# SCH_oscilliscope_copy_2021-09-11.net
KiCad netlist of a schematic drawn in EasyEDA
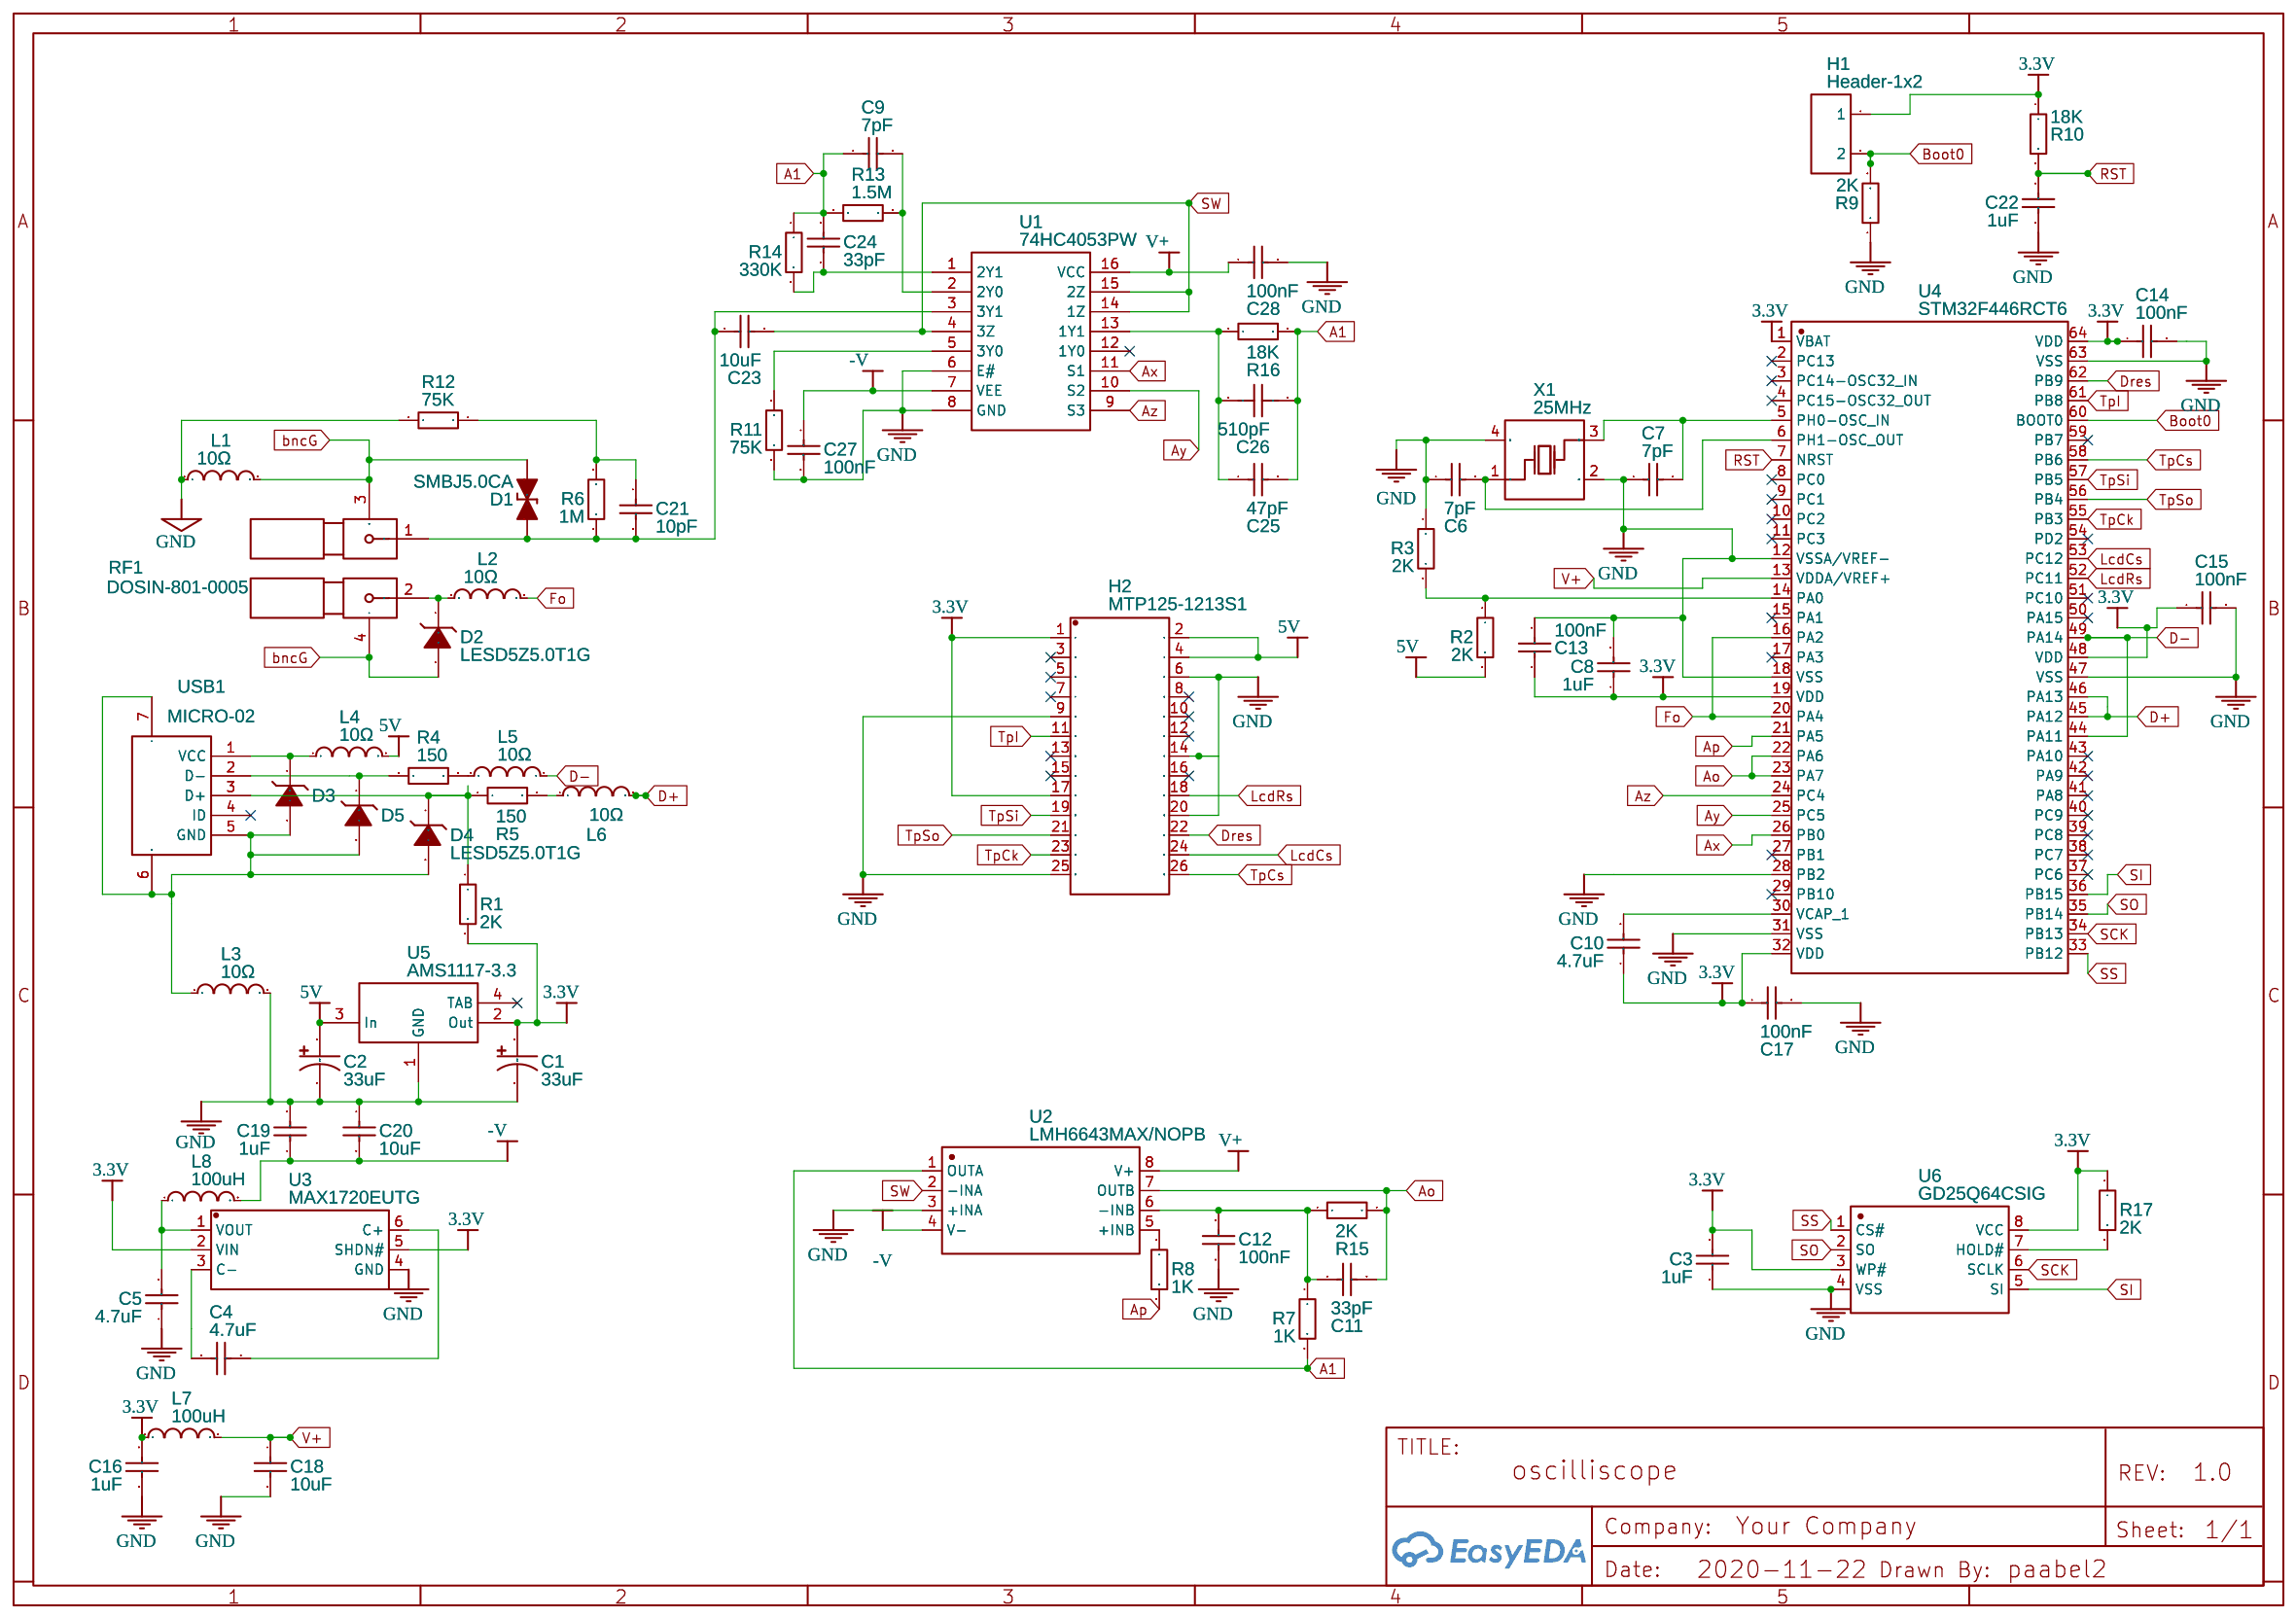
[diagram p0: schematic sheet]

(export (version "E")
  (design (tool "Eeschema 10.0.6"))
  (components
    (comp (ref "C1")
      (value "33uF")
      (fields
        (field (name "BOM_Manufacturer Part") "TC211A336M006Y")
        (field (name "BOM_Supplier Part") "C128344")
      )
      (libsource (lib "") (part "TC211A336M006Y"))
    )
    (comp (ref "C2")
      (value "33uF")
      (fields
        (field (name "BOM_Manufacturer Part") "TC211A336M006Y")
        (field (name "BOM_Supplier Part") "C128344")
      )
      (libsource (lib "") (part "TC211A336M006Y"))
    )
    (comp (ref "C3")
      (value "1uF")
      (fields
        (field (name "BOM_Manufacturer Part") "CL05A105KP5NNNC")
        (field (name "BOM_Supplier Part") "C14445")
      )
      (libsource (lib "") (part "CL05A105KP5NNNC"))
    )
    (comp (ref "C4")
      (value "4.7uF")
      (fields
        (field (name "BOM_Manufacturer Part") "CL21A475KAQNNNE")
        (field (name "BOM_Supplier Part") "C1779")
      )
      (libsource (lib "") (part "CL21A475KAQNNNE_1"))
    )
    (comp (ref "C5")
      (value "4.7uF")
      (fields
        (field (name "BOM_Manufacturer Part") "CL21A475KAQNNNE")
        (field (name "BOM_Supplier Part") "C1779")
      )
      (libsource (lib "") (part "CL21A475KAQNNNE"))
    )
    (comp (ref "C6")
      (value "7pF")
      (fields
        (field (name "BOM_Manufacturer Part") "0402CG7R0C500NT")
        (field (name "BOM_Supplier Part") "C1577")
      )
      (libsource (lib "") (part "0402CG7R0C500NT"))
    )
    (comp (ref "C7")
      (value "7pF")
      (fields
        (field (name "BOM_Manufacturer Part") "0402CG7R0C500NT")
        (field (name "BOM_Supplier Part") "C1577")
      )
      (libsource (lib "") (part "0402CG7R0C500NT"))
    )
    (comp (ref "C8")
      (value "1uF")
      (fields
        (field (name "BOM_Manufacturer Part") "CL05A105KP5NNNC")
        (field (name "BOM_Supplier Part") "C14445")
      )
      (libsource (lib "") (part "CL05A105KP5NNNC"))
    )
    (comp (ref "C9")
      (value "7pF")
      (fields
        (field (name "BOM_Manufacturer Part") "0402CG7R0C500NT")
        (field (name "BOM_Supplier Part") "C1577")
      )
      (libsource (lib "") (part "0402CG7R0C500NT"))
    )
    (comp (ref "C10")
      (value "4.7uF")
      (fields
        (field (name "BOM_Manufacturer Part") "CL21A475KAQNNNE")
        (field (name "BOM_Supplier Part") "C1779")
      )
      (libsource (lib "") (part "CL21A475KAQNNNE"))
    )
    (comp (ref "C11")
      (value "33pF")
      (fields
        (field (name "BOM_Manufacturer Part") "0402CG330J500NT")
        (field (name "BOM_Supplier Part") "C1562")
      )
      (libsource (lib "") (part "0402CG330J500NT"))
    )
    (comp (ref "C12")
      (value "100nF")
      (fields
        (field (name "BOM_Manufacturer Part") "CL05B104KO5NNNC")
        (field (name "BOM_Supplier Part") "C1525")
      )
      (libsource (lib "") (part "CL05B104KO5NNNC"))
    )
    (comp (ref "C13")
      (value "100nF")
      (fields
        (field (name "BOM_Manufacturer Part") "CL05B104KO5NNNC")
        (field (name "BOM_Supplier Part") "C1525")
      )
      (libsource (lib "") (part "CL05B104KO5NNNC_2"))
    )
    (comp (ref "C14")
      (value "100nF")
      (fields
        (field (name "BOM_Manufacturer Part") "CL05B104KO5NNNC")
        (field (name "BOM_Supplier Part") "C1525")
      )
      (libsource (lib "") (part "CL05B104KO5NNNC_1"))
    )
    (comp (ref "C15")
      (value "100nF")
      (fields
        (field (name "BOM_Manufacturer Part") "CL05B104KO5NNNC")
        (field (name "BOM_Supplier Part") "C1525")
      )
      (libsource (lib "") (part "CL05B104KO5NNNC_1"))
    )
    (comp (ref "C16")
      (value "1uF")
      (fields
        (field (name "BOM_Manufacturer Part") "CL05A105KP5NNNC")
        (field (name "BOM_Supplier Part") "C14445")
      )
      (libsource (lib "") (part "CL05A105KP5NNNC"))
    )
    (comp (ref "C17")
      (value "100nF")
      (fields
        (field (name "BOM_Manufacturer Part") "CL05B104KO5NNNC")
        (field (name "BOM_Supplier Part") "C1525")
      )
      (libsource (lib "") (part "CL05B104KO5NNNC_1"))
    )
    (comp (ref "C18")
      (value "10uF")
      (fields
        (field (name "BOM_Manufacturer Part") "CL21A106KAYNNNE")
        (field (name "BOM_Supplier Part") "C15850")
      )
      (libsource (lib "") (part "CL21A106KAYNNNE"))
    )
    (comp (ref "C19")
      (value "1uF")
      (fields
        (field (name "BOM_Manufacturer Part") "CL05A105KP5NNNC")
        (field (name "BOM_Supplier Part") "C14445")
      )
      (libsource (lib "") (part "CL05A105KP5NNNC"))
    )
    (comp (ref "C20")
      (value "10uF")
      (fields
        (field (name "BOM_Manufacturer Part") "CL21A106KAYNNNE")
        (field (name "BOM_Supplier Part") "C15850")
      )
      (libsource (lib "") (part "CL21A106KAYNNNE"))
    )
    (comp (ref "C21")
      (value "10pF")
      (fields
        (field (name "BOM_Manufacturer Part") "CL10C100JB8NNNC")
        (field (name "BOM_Supplier Part") "C1634")
      )
      (libsource (lib "") (part "CL10C100JB8NNNC"))
    )
    (comp (ref "C22")
      (value "1uF")
      (fields
        (field (name "BOM_Manufacturer Part") "CL05A105KP5NNNC")
        (field (name "BOM_Supplier Part") "C14445")
      )
      (libsource (lib "") (part "CL05A105KP5NNNC"))
    )
    (comp (ref "C23")
      (value "10uF")
      (fields
        (field (name "BOM_Manufacturer Part") "CL21A106KAYNNNE")
        (field (name "BOM_Supplier Part") "C15850")
      )
      (libsource (lib "") (part "CL21A106KAYNNNE_1"))
    )
    (comp (ref "C24")
      (value "33pF")
      (fields
        (field (name "BOM_Manufacturer Part") "0402CG330J500NT")
        (field (name "BOM_Supplier Part") "C1562")
      )
      (libsource (lib "") (part "0402CG330J500NT_1"))
    )
    (comp (ref "C25")
      (value "47pF")
      (fields
        (field (name "BOM_Manufacturer Part") "CL10C470JB8NNNC")
        (field (name "BOM_Supplier Part") "C1671")
      )
      (libsource (lib "") (part "CL10C470JB8NNNC"))
    )
    (comp (ref "C26")
      (value "510pF")
      (fields
        (field (name "BOM_Manufacturer Part") "CL10B511KB8NNNC")
        (field (name "BOM_Supplier Part") "C170144")
      )
      (libsource (lib "") (part "CL10B511KB8NNNC"))
    )
    (comp (ref "C27")
      (value "100nF")
      (fields
        (field (name "BOM_Manufacturer Part") "CL05B104KO5NNNC")
        (field (name "BOM_Supplier Part") "C1525")
      )
      (libsource (lib "") (part "CL05B104KO5NNNC"))
    )
    (comp (ref "C28")
      (value "100nF")
      (fields
        (field (name "BOM_Manufacturer Part") "CL05B104KO5NNNC")
        (field (name "BOM_Supplier Part") "C1525")
      )
      (libsource (lib "") (part "CL05B104KO5NNNC_1"))
    )
    (comp (ref "D1")
      (value "SMBJ5.0CA")
      (fields (field (name "BOM_Supplier Part") "C78424"))
      (libsource (lib "") (part "SMBJ5.0CA-C78424"))
    )
    (comp (ref "D2")
      (value "LESD5Z5.0T1G")
      (fields (field (name "BOM_Supplier Part") "C136171"))
      (libsource (lib "") (part "LESD5Z5.0T1G"))
    )
    (comp (ref "D3")
      (value "LESD5Z5.0T1G")
      (fields (field (name "BOM_Supplier Part") "C136171"))
      (libsource (lib "") (part "LESD5Z5.0T1G"))
    )
    (comp (ref "D4")
      (value "LESD5Z5.0T1G")
      (fields (field (name "BOM_Supplier Part") "C136171"))
      (libsource (lib "") (part "LESD5Z5.0T1G"))
    )
    (comp (ref "D5")
      (value "LESD5Z5.0T1G")
      (fields (field (name "BOM_Supplier Part") "C136171"))
      (libsource (lib "") (part "LESD5Z5.0T1G"))
    )
    (comp (ref "H1")
      (value "Header-1x2")
      (fields (field (name "BOM_Manufacturer Part") "826629-2") (field (name "BOM_Supplier Part") "C86471"))
      (libsource (lib "") (part "Header-Male-2.54_1x2"))
    )
    (comp (ref "H2")
      (value "MTP125-1213S1")
      (fields (field (name "BOM_Supplier Part") "C358701"))
      (libsource (lib "") (part "MTP125-1213S1"))
    )
    (comp (ref "L1")
      (value "10Ω")
      (fields
        (field (name "BOM_Manufacturer Part") "BLM15AG100SN1D")
        (field (name "BOM_Supplier Part") "C76882")
      )
      (libsource (lib "") (part "BLM15AG100SN1D"))
    )
    (comp (ref "L2")
      (value "10Ω")
      (fields
        (field (name "BOM_Manufacturer Part") "BLM15AG100SN1D")
        (field (name "BOM_Supplier Part") "C76882")
      )
      (libsource (lib "") (part "BLM15AG100SN1D_1"))
    )
    (comp (ref "L3")
      (value "10Ω")
      (fields
        (field (name "BOM_Manufacturer Part") "BLM15AG100SN1D")
        (field (name "BOM_Supplier Part") "C76882")
      )
      (libsource (lib "") (part "BLM15AG100SN1D"))
    )
    (comp (ref "L4")
      (value "10Ω")
      (fields
        (field (name "BOM_Manufacturer Part") "BLM15AG100SN1D")
        (field (name "BOM_Supplier Part") "C76882")
      )
      (libsource (lib "") (part "BLM15AG100SN1D_1"))
    )
    (comp (ref "L5")
      (value "10Ω")
      (fields
        (field (name "BOM_Manufacturer Part") "BLM15AG100SN1D")
        (field (name "BOM_Supplier Part") "C76882")
      )
      (libsource (lib "") (part "BLM15AG100SN1D_1"))
    )
    (comp (ref "L6")
      (value "10Ω")
      (fields
        (field (name "BOM_Manufacturer Part") "BLM15AG100SN1D")
        (field (name "BOM_Supplier Part") "C76882")
      )
      (libsource (lib "") (part "BLM15AG100SN1D_2"))
    )
    (comp (ref "L7")
      (value "100uH")
      (fields
        (field (name "BOM_Manufacturer Part") "SCCD32-101KT")
        (field (name "BOM_Supplier Part") "C532859")
      )
      (libsource (lib "") (part "SCCD32-101KT"))
    )
    (comp (ref "L8")
      (value "100uH")
      (fields
        (field (name "BOM_Manufacturer Part") "SCCD32-101KT")
        (field (name "BOM_Supplier Part") "C532859")
      )
      (libsource (lib "") (part "SCCD32-101KT"))
    )
    (comp (ref "R1")
      (value "2K")
      (fields
        (field (name "BOM_Manufacturer Part") "0603WAF2001T5E")
        (field (name "BOM_Supplier Part") "C22975")
      )
      (libsource (lib "") (part "0603WAF2001T5E"))
    )
    (comp (ref "R2")
      (value "2K")
      (fields
        (field (name "BOM_Manufacturer Part") "0603WAF2001T5E")
        (field (name "BOM_Supplier Part") "C22975")
      )
      (libsource (lib "") (part "0603WAF2001T5E"))
    )
    (comp (ref "R3")
      (value "2K")
      (fields
        (field (name "BOM_Manufacturer Part") "0603WAF2001T5E")
        (field (name "BOM_Supplier Part") "C22975")
      )
      (libsource (lib "") (part "0603WAF2001T5E"))
    )
    (comp (ref "R4")
      (value "150")
      (fields
        (field (name "BOM_Manufacturer Part") "0603WAF1500T5E")
        (field (name "BOM_Supplier Part") "C22808")
      )
      (libsource (lib "") (part "0603WAF1500T5E"))
    )
    (comp (ref "R5")
      (value "150")
      (fields
        (field (name "BOM_Manufacturer Part") "0603WAF1500T5E")
        (field (name "BOM_Supplier Part") "C22808")
      )
      (libsource (lib "") (part "0603WAF1500T5E"))
    )
    (comp (ref "R6")
      (value "1M")
      (fields
        (field (name "BOM_Manufacturer Part") "0603WAF1004T5E")
        (field (name "BOM_Supplier Part") "C22935")
      )
      (libsource (lib "") (part "0603WAF1004T5E"))
    )
    (comp (ref "R7")
      (value "1K")
      (fields
        (field (name "BOM_Manufacturer Part") "0603WAF1001T5E")
        (field (name "BOM_Supplier Part") "C21190")
      )
      (libsource (lib "") (part "0603WAF1001T5E"))
    )
    (comp (ref "R8")
      (value "1K")
      (fields
        (field (name "BOM_Manufacturer Part") "0603WAF1001T5E")
        (field (name "BOM_Supplier Part") "C21190")
      )
      (libsource (lib "") (part "0603WAF1001T5E"))
    )
    (comp (ref "R9")
      (value "2K")
      (fields
        (field (name "BOM_Manufacturer Part") "0603WAF2001T5E")
        (field (name "BOM_Supplier Part") "C22975")
      )
      (libsource (lib "") (part "0603WAF2001T5E_2"))
    )
    (comp (ref "R10")
      (value "18K")
      (fields
        (field (name "BOM_Manufacturer Part") "0603WAF1802T5E")
        (field (name "BOM_Supplier Part") "C25810")
      )
      (libsource (lib "") (part "0603WAF1802T5E_1"))
    )
    (comp (ref "R11")
      (value "75K")
      (fields
        (field (name "BOM_Manufacturer Part") "0603WAF7502T5E")
        (field (name "BOM_Supplier Part") "C23242")
      )
      (libsource (lib "") (part "0603WAF7502T5E_1"))
    )
    (comp (ref "R12")
      (value "75K")
      (fields
        (field (name "BOM_Manufacturer Part") "0603WAF7502T5E")
        (field (name "BOM_Supplier Part") "C23242")
      )
      (libsource (lib "") (part "0603WAF7502T5E"))
    )
    (comp (ref "R13")
      (value "1.5M")
      (fields
        (field (name "BOM_Manufacturer Part") "0603WAF1504T5E")
        (field (name "BOM_Supplier Part") "C4172")
      )
      (libsource (lib "") (part "0603WAF1504T5E"))
    )
    (comp (ref "R14")
      (value "330K")
      (fields
        (field (name "BOM_Manufacturer Part") "RTT03334JTP")
        (field (name "BOM_Supplier Part") "C103555")
      )
      (libsource (lib "") (part "RTT03334JTP"))
    )
    (comp (ref "R15")
      (value "2K")
      (fields
        (field (name "BOM_Manufacturer Part") "0603WAF2001T5E")
        (field (name "BOM_Supplier Part") "C22975")
      )
      (libsource (lib "") (part "0603WAF2001T5E_1"))
    )
    (comp (ref "R16")
      (value "18K")
      (fields
        (field (name "BOM_Manufacturer Part") "0603WAF1802T5E")
        (field (name "BOM_Supplier Part") "C25810")
      )
      (libsource (lib "") (part "0603WAF1802T5E"))
    )
    (comp (ref "R17")
      (value "2K")
      (fields
        (field (name "BOM_Manufacturer Part") "0603WAF2001T5E")
        (field (name "BOM_Supplier Part") "C22975")
      )
      (libsource (lib "") (part "0603WAF2001T5E"))
    )
    (comp (ref "RF1")
      (value "DOSIN-801-0005")
      (fields (field (name "BOM_Supplier Part") "C521213"))
      (libsource (lib "") (part "DOSIN-801-0005"))
    )
    (comp (ref "U1")
      (value "74HC4053PW")
      (fields (field (name "BOM_Supplier Part") "C5648"))
      (libsource (lib "") (part "74HC4053PW"))
    )
    (comp (ref "U2")
      (value "LMH6643MAX/NOPB")
      (fields (field (name "BOM_Supplier Part") "C44880"))
      (libsource (lib "") (part "LMH6643MAX/NOPB"))
    )
    (comp (ref "U3")
      (value "MAX1720EUTG")
      (fields (field (name "BOM_Supplier Part") "C70466"))
      (libsource (lib "") (part "MAX1720EUTG"))
    )
    (comp (ref "U4")
      (value "STM32F446RCT6")
      (fields
        (field (name "BOM_Manufacturer Part") "STM32F446RET6")
        (field (name "BOM_Supplier Part") "C69336")
      )
      (libsource (lib "") (part "STM32F446RET6"))
    )
    (comp (ref "U5")
      (value "AMS1117-3.3")
      (fields (field (name "BOM_Supplier Part") "C165482"))
      (libsource (lib "") (part "AMS1117-3.3_C165482"))
    )
    (comp (ref "U6")
      (value "GD25Q64CSIG")
      (fields (field (name "BOM_Supplier Part") "C79076"))
      (libsource (lib "") (part "GD25Q64CSIG"))
    )
    (comp (ref "USB1")
      (value "MICRO-02")
      (fields
        (field (name "BOM_Manufacturer Part") "MICRO-02-G1P3-A1T2")
        (field (name "BOM_Supplier Part") "C2682518")
      )
      (libsource (lib "") (part "MICRO-02-G1P3-A1T2"))
    )
    (comp (ref "X1")
      (value "25MHz")
      (fields
        (field (name "BOM_Manufacturer Part") "X322525MOB4SI")
        (field (name "BOM_Supplier Part") "C9006")
      )
      (libsource (lib "") (part "X322525MOB4SI"))
    )
  )
  (nets
    (net (code "1") (name "-V") (class "Default")
      (node (ref "C19") (pin "1") (pinfunction "1_1") (pintype "input"))
      (node (ref "C20") (pin "2") (pinfunction "2_2") (pintype "input"))
      (node (ref "C27") (pin "1") (pinfunction "1_1") (pintype "input"))
      (node (ref "L8") (pin "2") (pinfunction "2_2") (pintype "unspecified"))
      (node (ref "U1") (pin "7") (pinfunction "VEE_7") (pintype "unspecified"))
      (node (ref "U2") (pin "4") (pinfunction "V-_4") (pintype "unspecified"))
    )
    (net (code "2") (name "3.3V") (class "Default")
      (node (ref "C1") (pin "1") (pinfunction "1_1") (pintype "unspecified"))
      (node (ref "C10") (pin "1") (pinfunction "1_1") (pintype "input"))
      (node (ref "C13") (pin "1") (pinfunction "1_1") (pintype "input"))
      (node (ref "C14") (pin "1") (pinfunction "1_1") (pintype "input"))
      (node (ref "C15") (pin "1") (pinfunction "1_1") (pintype "input"))
      (node (ref "C16") (pin "2") (pinfunction "2_2") (pintype "input"))
      (node (ref "C17") (pin "1") (pinfunction "1_1") (pintype "input"))
      (node (ref "C3") (pin "2") (pinfunction "2_2") (pintype "input"))
      (node (ref "C8") (pin "1") (pinfunction "1_1") (pintype "input"))
      (node (ref "H1") (pin "1") (pinfunction "1_1") (pintype "unspecified"))
      (node (ref "H2") (pin "1") (pinfunction "1_1") (pintype "unspecified"))
      (node (ref "H2") (pin "17") (pinfunction "17_17") (pintype "unspecified"))
      (node (ref "L7") (pin "1") (pinfunction "1_1") (pintype "unspecified"))
      (node (ref "R1") (pin "2") (pinfunction "2_2") (pintype "input"))
      (node (ref "R10") (pin "1") (pinfunction "1_1") (pintype "input"))
      (node (ref "R17") (pin "1") (pinfunction "1_1") (pintype "input"))
      (node (ref "U3") (pin "2") (pinfunction "VIN_2") (pintype "unspecified"))
      (node (ref "U3") (pin "5") (pinfunction "SHDN#_5") (pintype "unspecified"))
      (node (ref "U4") (pin "1") (pinfunction "VBAT_1") (pintype "unspecified"))
      (node (ref "U4") (pin "19") (pinfunction "VDD_19") (pintype "unspecified"))
      (node (ref "U4") (pin "32") (pinfunction "VDD_32") (pintype "unspecified"))
      (node (ref "U4") (pin "48") (pinfunction "VDD_48") (pintype "unspecified"))
      (node (ref "U4") (pin "64") (pinfunction "VDD_64") (pintype "unspecified"))
      (node (ref "U5") (pin "2") (pinfunction "Out_2") (pintype "unspecified"))
      (node (ref "U6") (pin "3") (pinfunction "WP#_3") (pintype "unspecified"))
      (node (ref "U6") (pin "8") (pinfunction "VCC_8") (pintype "unspecified"))
    )
    (net (code "3") (name "5V") (class "Default")
      (node (ref "C2") (pin "1") (pinfunction "1_1") (pintype "unspecified"))
      (node (ref "H2") (pin "2") (pinfunction "2_2") (pintype "unspecified"))
      (node (ref "H2") (pin "4") (pinfunction "4_4") (pintype "unspecified"))
      (node (ref "L4") (pin "2") (pinfunction "2_2") (pintype "unspecified"))
      (node (ref "R2") (pin "2") (pinfunction "2_2") (pintype "input"))
      (node (ref "U5") (pin "3") (pinfunction "In_3") (pintype "unspecified"))
    )
    (net (code "4") (name "A1") (class "Default")
      (node (ref "C24") (pin "2") (pinfunction "2_2") (pintype "input"))
      (node (ref "C25") (pin "2") (pinfunction "2_2") (pintype "input"))
      (node (ref "C26") (pin "1") (pinfunction "1_1") (pintype "unspecified"))
      (node (ref "C9") (pin "1") (pinfunction "1_1") (pintype "input"))
      (node (ref "R13") (pin "1") (pinfunction "1_1") (pintype "input"))
      (node (ref "R14") (pin "1") (pinfunction "1_1") (pintype "input"))
      (node (ref "R16") (pin "2") (pinfunction "2_2") (pintype "input"))
      (node (ref "R7") (pin "2") (pinfunction "2_2") (pintype "input"))
      (node (ref "U2") (pin "1") (pinfunction "OUTA_1") (pintype "unspecified"))
    )
    (net (code "5") (name "Ao") (class "Default")
      (node (ref "C11") (pin "2") (pinfunction "2_2") (pintype "input"))
      (node (ref "R15") (pin "2") (pinfunction "2_2") (pintype "input"))
      (node (ref "U2") (pin "7") (pinfunction "OUTB_7") (pintype "unspecified"))
      (node (ref "U4") (pin "22") (pinfunction "PA6_22") (pintype "unspecified"))
      (node (ref "U4") (pin "23") (pinfunction "PA7_23") (pintype "unspecified"))
    )
    (net (code "6") (name "Ap") (class "Default")
      (node (ref "R8") (pin "2") (pinfunction "2_2") (pintype "input"))
      (node (ref "U4") (pin "21") (pinfunction "PA5_21") (pintype "unspecified"))
    )
    (net (code "7") (name "Ax") (class "Default")
      (node (ref "U1") (pin "11") (pinfunction "S1_11") (pintype "unspecified"))
      (node (ref "U4") (pin "26") (pinfunction "PB0_26") (pintype "unspecified"))
    )
    (net (code "8") (name "Ay") (class "Default")
      (node (ref "U1") (pin "10") (pinfunction "S2_10") (pintype "unspecified"))
      (node (ref "U4") (pin "25") (pinfunction "PC5_25") (pintype "unspecified"))
    )
    (net (code "9") (name "Az") (class "Default")
      (node (ref "U1") (pin "9") (pinfunction "S3_9") (pintype "unspecified"))
      (node (ref "U4") (pin "24") (pinfunction "PC4_24") (pintype "unspecified"))
    )
    (net (code "10") (name "Boot0") (class "Default")
      (node (ref "H1") (pin "2") (pinfunction "2_2") (pintype "unspecified"))
      (node (ref "R9") (pin "2") (pinfunction "2_2") (pintype "input"))
      (node (ref "U4") (pin "60") (pinfunction "BOOT0_60") (pintype "unspecified"))
    )
    (net (code "11") (name "D+") (class "Default")
      (node (ref "L6") (pin "2") (pinfunction "2_2") (pintype "unspecified"))
      (node (ref "U4") (pin "45") (pinfunction "PA12_45") (pintype "unspecified"))
      (node (ref "U4") (pin "46") (pinfunction "PA13_46") (pintype "unspecified"))
    )
    (net (code "12") (name "D-") (class "Default")
      (node (ref "L5") (pin "2") (pinfunction "2_2") (pintype "unspecified"))
      (node (ref "U4") (pin "44") (pinfunction "PA11_44") (pintype "unspecified"))
      (node (ref "U4") (pin "49") (pinfunction "PA14_49") (pintype "unspecified"))
    )
    (net (code "13") (name "Dres") (class "Default")
      (node (ref "H2") (pin "22") (pinfunction "22_22") (pintype "unspecified"))
      (node (ref "U4") (pin "62") (pinfunction "PB9_62") (pintype "unspecified"))
    )
    (net (code "14") (name "Fo") (class "Default")
      (node (ref "L2") (pin "2") (pinfunction "2_2") (pintype "unspecified"))
      (node (ref "U4") (pin "16") (pinfunction "PA2_16") (pintype "unspecified"))
      (node (ref "U4") (pin "20") (pinfunction "PA4_20") (pintype "unspecified"))
    )
    (net (code "15") (name "GND") (class "Default")
      (node (ref "C1") (pin "2") (pinfunction "2_2") (pintype "unspecified"))
      (node (ref "C12") (pin "2") (pinfunction "2_2") (pintype "input"))
      (node (ref "C13") (pin "2") (pinfunction "2_2") (pintype "input"))
      (node (ref "C14") (pin "2") (pinfunction "2_2") (pintype "input"))
      (node (ref "C15") (pin "2") (pinfunction "2_2") (pintype "input"))
      (node (ref "C16") (pin "1") (pinfunction "1_1") (pintype "input"))
      (node (ref "C17") (pin "2") (pinfunction "2_2") (pintype "input"))
      (node (ref "C18") (pin "2") (pinfunction "2_2") (pintype "input"))
      (node (ref "C19") (pin "2") (pinfunction "2_2") (pintype "input"))
      (node (ref "C2") (pin "2") (pinfunction "2_2") (pintype "unspecified"))
      (node (ref "C20") (pin "1") (pinfunction "1_1") (pintype "input"))
      (node (ref "C22") (pin "1") (pinfunction "1_1") (pintype "input"))
      (node (ref "C27") (pin "2") (pinfunction "2_2") (pintype "input"))
      (node (ref "C28") (pin "2") (pinfunction "2_2") (pintype "input"))
      (node (ref "C3") (pin "1") (pinfunction "1_1") (pintype "input"))
      (node (ref "C5") (pin "1") (pinfunction "1_1") (pintype "input"))
      (node (ref "C6") (pin "1") (pinfunction "1_1") (pintype "input"))
      (node (ref "C7") (pin "1") (pinfunction "1_1") (pintype "input"))
      (node (ref "C8") (pin "2") (pinfunction "2_2") (pintype "input"))
      (node (ref "H2") (pin "14") (pinfunction "14_14") (pintype "unspecified"))
      (node (ref "H2") (pin "20") (pinfunction "20_20") (pintype "unspecified"))
      (node (ref "H2") (pin "25") (pinfunction "25_25") (pintype "unspecified"))
      (node (ref "H2") (pin "6") (pinfunction "6_6") (pintype "unspecified"))
      (node (ref "H2") (pin "9") (pinfunction "9_9") (pintype "unspecified"))
      (node (ref "L1") (pin "1") (pinfunction "1_1") (pintype "unspecified"))
      (node (ref "L3") (pin "2") (pinfunction "2_2") (pintype "unspecified"))
      (node (ref "R11") (pin "1") (pinfunction "1_1") (pintype "input"))
      (node (ref "R12") (pin "2") (pinfunction "2_2") (pintype "input"))
      (node (ref "R3") (pin "1") (pinfunction "1_1") (pintype "input"))
      (node (ref "R9") (pin "1") (pinfunction "1_1") (pintype "input"))
      (node (ref "U1") (pin "6") (pinfunction "E#_6") (pintype "unspecified"))
      (node (ref "U1") (pin "8") (pinfunction "GND_8") (pintype "unspecified"))
      (node (ref "U2") (pin "3") (pinfunction "+INA_3") (pintype "unspecified"))
      (node (ref "U3") (pin "4") (pinfunction "GND_4") (pintype "unspecified"))
      (node (ref "U4") (pin "12") (pinfunction "VSSA/VREF-_12") (pintype "unspecified"))
      (node (ref "U4") (pin "18") (pinfunction "VSS_18") (pintype "unspecified"))
      (node (ref "U4") (pin "28") (pinfunction "PB2_28") (pintype "unspecified"))
      (node (ref "U4") (pin "31") (pinfunction "VSS_31") (pintype "unspecified"))
      (node (ref "U4") (pin "47") (pinfunction "VSS_47") (pintype "unspecified"))
      (node (ref "U4") (pin "63") (pinfunction "VSS_63") (pintype "unspecified"))
      (node (ref "U5") (pin "1") (pinfunction "GND_1") (pintype "unspecified"))
      (node (ref "U6") (pin "4") (pinfunction "VSS_4") (pintype "unspecified"))
      (node (ref "X1") (pin "2") (pinfunction "GND_2") (pintype "unspecified"))
      (node (ref "X1") (pin "4") (pinfunction "GND_4") (pintype "unspecified"))
    )
    (net (code "16") (name "LcdCs") (class "Default")
      (node (ref "H2") (pin "24") (pinfunction "24_24") (pintype "unspecified"))
      (node (ref "U4") (pin "53") (pinfunction "PC12_53") (pintype "unspecified"))
    )
    (net (code "17") (name "LcdRs") (class "Default")
      (node (ref "H2") (pin "18") (pinfunction "18_18") (pintype "unspecified"))
      (node (ref "U4") (pin "52") (pinfunction "PC11_52") (pintype "unspecified"))
    )
    (net (code "18") (name "Net-(C21-Pad1)") (class "Default")
      (node (ref "C21") (pin "1") (pinfunction "1_1") (pintype "input"))
      (node (ref "R12") (pin "1") (pinfunction "1_1") (pintype "input"))
      (node (ref "R6") (pin "2") (pinfunction "2_2") (pintype "input"))
    )
    (net (code "19") (name "Net-(D2-C)") (class "Default")
      (node (ref "D2") (pin "1") (pinfunction "C_1") (pintype "unspecified"))
      (node (ref "L2") (pin "1") (pinfunction "1_1") (pintype "unspecified"))
      (node (ref "RF1") (pin "2") (pinfunction "2_2") (pintype "unspecified"))
    )
    (net (code "20") (name "Net-(D3-A)") (class "Default")
      (node (ref "D3") (pin "2") (pinfunction "A_2") (pintype "unspecified"))
      (node (ref "D4") (pin "2") (pinfunction "A_2") (pintype "unspecified"))
      (node (ref "D5") (pin "2") (pinfunction "A_2") (pintype "unspecified"))
      (node (ref "L3") (pin "1") (pinfunction "1_1") (pintype "unspecified"))
      (node (ref "USB1") (pin "5") (pinfunction "GND_5") (pintype "input"))
      (node (ref "USB1") (pin "6") (pinfunction "6_6") (pintype "input"))
      (node (ref "USB1") (pin "7") (pinfunction "7_7") (pintype "input"))
    )
    (net (code "21") (name "Net-(D3-C)") (class "Default")
      (node (ref "D3") (pin "1") (pinfunction "C_1") (pintype "unspecified"))
      (node (ref "L4") (pin "1") (pinfunction "1_1") (pintype "unspecified"))
      (node (ref "USB1") (pin "1") (pinfunction "VCC_1") (pintype "input"))
    )
    (net (code "22") (name "Net-(D4-C)") (class "Default")
      (node (ref "D4") (pin "1") (pinfunction "C_1") (pintype "unspecified"))
      (node (ref "R1") (pin "1") (pinfunction "1_1") (pintype "input"))
      (node (ref "R5") (pin "1") (pinfunction "1_1") (pintype "input"))
      (node (ref "USB1") (pin "3") (pinfunction "D+_3") (pintype "input"))
    )
    (net (code "23") (name "Net-(D5-C)") (class "Default")
      (node (ref "D5") (pin "1") (pinfunction "C_1") (pintype "unspecified"))
      (node (ref "R4") (pin "1") (pinfunction "1_1") (pintype "input"))
      (node (ref "USB1") (pin "2") (pinfunction "D-_2") (pintype "input"))
    )
    (net (code "24") (name "Net-(L5-Pad1)") (class "Default")
      (node (ref "L5") (pin "1") (pinfunction "1_1") (pintype "unspecified"))
      (node (ref "R4") (pin "2") (pinfunction "2_2") (pintype "input"))
    )
    (net (code "25") (name "Net-(L6-Pad1)") (class "Default")
      (node (ref "L6") (pin "1") (pinfunction "1_1") (pintype "unspecified"))
      (node (ref "R5") (pin "2") (pinfunction "2_2") (pintype "input"))
    )
    (net (code "26") (name "Net-(U1-1Y1)") (class "Default")
      (node (ref "C25") (pin "1") (pinfunction "1_1") (pintype "input"))
      (node (ref "C26") (pin "2") (pinfunction "2_2") (pintype "unspecified"))
      (node (ref "R16") (pin "1") (pinfunction "1_1") (pintype "input"))
      (node (ref "U1") (pin "13") (pinfunction "1Y1_13") (pintype "unspecified"))
    )
    (net (code "27") (name "Net-(U1-2Y0)") (class "Default")
      (node (ref "C9") (pin "2") (pinfunction "2_2") (pintype "input"))
      (node (ref "R13") (pin "2") (pinfunction "2_2") (pintype "input"))
      (node (ref "U1") (pin "2") (pinfunction "2Y0_2") (pintype "unspecified"))
    )
    (net (code "28") (name "Net-(U1-2Y1)") (class "Default")
      (node (ref "C24") (pin "1") (pinfunction "1_1") (pintype "input"))
      (node (ref "R14") (pin "2") (pinfunction "2_2") (pintype "input"))
      (node (ref "U1") (pin "1") (pinfunction "2Y1_1") (pintype "unspecified"))
    )
    (net (code "29") (name "Net-(U1-3Y0)") (class "Default")
      (node (ref "R11") (pin "2") (pinfunction "2_2") (pintype "input"))
      (node (ref "U1") (pin "5") (pinfunction "3Y0_5") (pintype "unspecified"))
    )
    (net (code "30") (name "Net-(U1-3Y1)") (class "Default")
      (node (ref "C21") (pin "2") (pinfunction "2_2") (pintype "input"))
      (node (ref "C23") (pin "1") (pinfunction "1_1") (pintype "input"))
      (node (ref "D1") (pin "2") (pinfunction "2_2") (pintype "unspecified"))
      (node (ref "R6") (pin "1") (pinfunction "1_1") (pintype "input"))
      (node (ref "RF1") (pin "1") (pinfunction "1_1") (pintype "unspecified"))
      (node (ref "U1") (pin "3") (pinfunction "3Y1_3") (pintype "unspecified"))
    )
    (net (code "31") (name "Net-(U2-+INB)") (class "Default")
      (node (ref "R8") (pin "1") (pinfunction "1_1") (pintype "input"))
      (node (ref "U2") (pin "5") (pinfunction "+INB_5") (pintype "unspecified"))
    )
    (net (code "32") (name "Net-(U2--INB)") (class "Default")
      (node (ref "C11") (pin "1") (pinfunction "1_1") (pintype "input"))
      (node (ref "C12") (pin "1") (pinfunction "1_1") (pintype "input"))
      (node (ref "R15") (pin "1") (pinfunction "1_1") (pintype "input"))
      (node (ref "R7") (pin "1") (pinfunction "1_1") (pintype "input"))
      (node (ref "U2") (pin "6") (pinfunction "-INB_6") (pintype "unspecified"))
    )
    (net (code "33") (name "Net-(U3-C+)") (class "Default")
      (node (ref "C4") (pin "2") (pinfunction "2_2") (pintype "input"))
      (node (ref "U3") (pin "6") (pinfunction "C+_6") (pintype "unspecified"))
    )
    (net (code "34") (name "Net-(U3-C-)") (class "Default")
      (node (ref "C4") (pin "1") (pinfunction "1_1") (pintype "input"))
      (node (ref "U3") (pin "3") (pinfunction "C-_3") (pintype "unspecified"))
    )
    (net (code "35") (name "Net-(U3-VOUT)") (class "Default")
      (node (ref "C5") (pin "2") (pinfunction "2_2") (pintype "input"))
      (node (ref "L8") (pin "1") (pinfunction "1_1") (pintype "unspecified"))
      (node (ref "U3") (pin "1") (pinfunction "VOUT_1") (pintype "unspecified"))
    )
    (net (code "36") (name "Net-(U4-PA0)") (class "Default")
      (node (ref "R2") (pin "1") (pinfunction "1_1") (pintype "input"))
      (node (ref "R3") (pin "2") (pinfunction "2_2") (pintype "input"))
      (node (ref "U4") (pin "14") (pinfunction "PA0_14") (pintype "unspecified"))
    )
    (net (code "37") (name "Net-(U4-PH0-OSC_IN)") (class "Default")
      (node (ref "C7") (pin "2") (pinfunction "2_2") (pintype "input"))
      (node (ref "U4") (pin "5") (pinfunction "PH0-OSC_IN_5") (pintype "unspecified"))
      (node (ref "X1") (pin "3") (pinfunction "OSC2_3") (pintype "unspecified"))
    )
    (net (code "38") (name "Net-(U4-PH1-OSC_OUT)") (class "Default")
      (node (ref "C6") (pin "2") (pinfunction "2_2") (pintype "input"))
      (node (ref "U4") (pin "6") (pinfunction "PH1-OSC_OUT_6") (pintype "unspecified"))
      (node (ref "X1") (pin "1") (pinfunction "OSC1_1") (pintype "unspecified"))
    )
    (net (code "39") (name "Net-(U4-VCAP_1)") (class "Default")
      (node (ref "C10") (pin "2") (pinfunction "2_2") (pintype "input"))
      (node (ref "U4") (pin "30") (pinfunction "VCAP_1_30") (pintype "unspecified"))
    )
    (net (code "40") (name "Net-(U6-HOLD#)") (class "Default")
      (node (ref "R17") (pin "2") (pinfunction "2_2") (pintype "input"))
      (node (ref "U6") (pin "7") (pinfunction "HOLD#_7") (pintype "unspecified"))
    )
    (net (code "41") (name "RST") (class "Default")
      (node (ref "C22") (pin "2") (pinfunction "2_2") (pintype "input"))
      (node (ref "R10") (pin "2") (pinfunction "2_2") (pintype "input"))
      (node (ref "U4") (pin "7") (pinfunction "NRST_7") (pintype "unspecified"))
    )
    (net (code "42") (name "SCK") (class "Default")
      (node (ref "U4") (pin "34") (pinfunction "PB13_34") (pintype "unspecified"))
      (node (ref "U6") (pin "6") (pinfunction "SCLK_6") (pintype "unspecified"))
    )
    (net (code "43") (name "SI") (class "Default")
      (node (ref "U4") (pin "36") (pinfunction "PB15_36") (pintype "unspecified"))
      (node (ref "U6") (pin "5") (pinfunction "SI_5") (pintype "unspecified"))
    )
    (net (code "44") (name "SO") (class "Default")
      (node (ref "U4") (pin "35") (pinfunction "PB14_35") (pintype "unspecified"))
      (node (ref "U6") (pin "2") (pinfunction "SO_2") (pintype "unspecified"))
    )
    (net (code "45") (name "SS") (class "Default")
      (node (ref "U4") (pin "33") (pinfunction "PB12_33") (pintype "unspecified"))
      (node (ref "U6") (pin "1") (pinfunction "CS#_1") (pintype "unspecified"))
    )
    (net (code "46") (name "SW") (class "Default")
      (node (ref "C23") (pin "2") (pinfunction "2_2") (pintype "input"))
      (node (ref "U1") (pin "14") (pinfunction "1Z_14") (pintype "unspecified"))
      (node (ref "U1") (pin "15") (pinfunction "2Z_15") (pintype "unspecified"))
      (node (ref "U1") (pin "4") (pinfunction "3Z_4") (pintype "unspecified"))
      (node (ref "U2") (pin "2") (pinfunction "-INA_2") (pintype "unspecified"))
    )
    (net (code "47") (name "TpCk") (class "Default")
      (node (ref "H2") (pin "23") (pinfunction "23_23") (pintype "unspecified"))
      (node (ref "U4") (pin "55") (pinfunction "PB3_55") (pintype "unspecified"))
    )
    (net (code "48") (name "TpCs") (class "Default")
      (node (ref "H2") (pin "26") (pinfunction "26_26") (pintype "unspecified"))
      (node (ref "U4") (pin "58") (pinfunction "PB6_58") (pintype "unspecified"))
    )
    (net (code "49") (name "TpI") (class "Default")
      (node (ref "H2") (pin "11") (pinfunction "11_11") (pintype "unspecified"))
      (node (ref "U4") (pin "61") (pinfunction "PB8_61") (pintype "unspecified"))
    )
    (net (code "50") (name "TpSi") (class "Default")
      (node (ref "H2") (pin "19") (pinfunction "19_19") (pintype "unspecified"))
      (node (ref "U4") (pin "57") (pinfunction "PB5_57") (pintype "unspecified"))
    )
    (net (code "51") (name "TpSo") (class "Default")
      (node (ref "H2") (pin "21") (pinfunction "21_21") (pintype "unspecified"))
      (node (ref "U4") (pin "56") (pinfunction "PB4_56") (pintype "unspecified"))
    )
    (net (code "52") (name "V+") (class "Default")
      (node (ref "C18") (pin "1") (pinfunction "1_1") (pintype "input"))
      (node (ref "C28") (pin "1") (pinfunction "1_1") (pintype "input"))
      (node (ref "L7") (pin "2") (pinfunction "2_2") (pintype "unspecified"))
      (node (ref "U1") (pin "16") (pinfunction "VCC_16") (pintype "unspecified"))
      (node (ref "U2") (pin "8") (pinfunction "V+_8") (pintype "unspecified"))
      (node (ref "U4") (pin "13") (pinfunction "VDDA/VREF+_13") (pintype "unspecified"))
    )
    (net (code "53") (name "bncG") (class "Default")
      (node (ref "D1") (pin "1") (pinfunction "1_1") (pintype "unspecified"))
      (node (ref "D2") (pin "2") (pinfunction "A_2") (pintype "unspecified"))
      (node (ref "L1") (pin "2") (pinfunction "2_2") (pintype "unspecified"))
      (node (ref "RF1") (pin "3") (pinfunction "3_3") (pintype "unspecified"))
      (node (ref "RF1") (pin "4") (pinfunction "4_4") (pintype "unspecified"))
    )
    (net (code "54") (name "unconnected-(H2-Pad3)") (class "Default")
      (node (ref "H2") (pin "3") (pinfunction "3_3") (pintype "unspecified+no_connect"))
    )
    (net (code "55") (name "unconnected-(H2-Pad5)") (class "Default")
      (node (ref "H2") (pin "5") (pinfunction "5_5") (pintype "unspecified+no_connect"))
    )
    (net (code "56") (name "unconnected-(H2-Pad7)") (class "Default")
      (node (ref "H2") (pin "7") (pinfunction "7_7") (pintype "unspecified+no_connect"))
    )
    (net (code "57") (name "unconnected-(H2-Pad8)") (class "Default")
      (node (ref "H2") (pin "8") (pinfunction "8_8") (pintype "unspecified+no_connect"))
    )
    (net (code "58") (name "unconnected-(H2-Pad10)") (class "Default")
      (node (ref "H2") (pin "10") (pinfunction "10_10") (pintype "unspecified+no_connect"))
    )
    (net (code "59") (name "unconnected-(H2-Pad12)") (class "Default")
      (node (ref "H2") (pin "12") (pinfunction "12_12") (pintype "unspecified+no_connect"))
    )
    (net (code "60") (name "unconnected-(H2-Pad13)") (class "Default")
      (node (ref "H2") (pin "13") (pinfunction "13_13") (pintype "unspecified+no_connect"))
    )
    (net (code "61") (name "unconnected-(H2-Pad15)") (class "Default")
      (node (ref "H2") (pin "15") (pinfunction "15_15") (pintype "unspecified+no_connect"))
    )
    (net (code "62") (name "unconnected-(H2-Pad16)") (class "Default")
      (node (ref "H2") (pin "16") (pinfunction "16_16") (pintype "unspecified+no_connect"))
    )
    (net (code "63") (name "unconnected-(U1-1Y0-Pad12)") (class "Default")
      (node (ref "U1") (pin "12") (pinfunction "1Y0_12") (pintype "unspecified+no_connect"))
    )
    (net (code "64") (name "unconnected-(U4-PA1-Pad15)") (class "Default")
      (node (ref "U4") (pin "15") (pinfunction "PA1_15") (pintype "unspecified+no_connect"))
    )
    (net (code "65") (name "unconnected-(U4-PA3-Pad17)") (class "Default")
      (node (ref "U4") (pin "17") (pinfunction "PA3_17") (pintype "unspecified+no_connect"))
    )
    (net (code "66") (name "unconnected-(U4-PA8-Pad41)") (class "Default")
      (node (ref "U4") (pin "41") (pinfunction "PA8_41") (pintype "unspecified+no_connect"))
    )
    (net (code "67") (name "unconnected-(U4-PA9-Pad42)") (class "Default")
      (node (ref "U4") (pin "42") (pinfunction "PA9_42") (pintype "unspecified+no_connect"))
    )
    (net (code "68") (name "unconnected-(U4-PA10-Pad43)") (class "Default")
      (node (ref "U4") (pin "43") (pinfunction "PA10_43") (pintype "unspecified+no_connect"))
    )
    (net (code "69") (name "unconnected-(U4-PA15-Pad50)") (class "Default")
      (node (ref "U4") (pin "50") (pinfunction "PA15_50") (pintype "unspecified+no_connect"))
    )
    (net (code "70") (name "unconnected-(U4-PB1-Pad27)") (class "Default")
      (node (ref "U4") (pin "27") (pinfunction "PB1_27") (pintype "unspecified+no_connect"))
    )
    (net (code "71") (name "unconnected-(U4-PB7-Pad59)") (class "Default")
      (node (ref "U4") (pin "59") (pinfunction "PB7_59") (pintype "unspecified+no_connect"))
    )
    (net (code "72") (name "unconnected-(U4-PB10-Pad29)") (class "Default")
      (node (ref "U4") (pin "29") (pinfunction "PB10_29") (pintype "unspecified+no_connect"))
    )
    (net (code "73") (name "unconnected-(U4-PC0-Pad8)") (class "Default")
      (node (ref "U4") (pin "8") (pinfunction "PC0_8") (pintype "unspecified+no_connect"))
    )
    (net (code "74") (name "unconnected-(U4-PC1-Pad9)") (class "Default")
      (node (ref "U4") (pin "9") (pinfunction "PC1_9") (pintype "unspecified+no_connect"))
    )
    (net (code "75") (name "unconnected-(U4-PC2-Pad10)") (class "Default")
      (node (ref "U4") (pin "10") (pinfunction "PC2_10") (pintype "unspecified+no_connect"))
    )
    (net (code "76") (name "unconnected-(U4-PC3-Pad11)") (class "Default")
      (node (ref "U4") (pin "11") (pinfunction "PC3_11") (pintype "unspecified+no_connect"))
    )
    (net (code "77") (name "unconnected-(U4-PC6-Pad37)") (class "Default")
      (node (ref "U4") (pin "37") (pinfunction "PC6_37") (pintype "unspecified+no_connect"))
    )
    (net (code "78") (name "unconnected-(U4-PC7-Pad38)") (class "Default")
      (node (ref "U4") (pin "38") (pinfunction "PC7_38") (pintype "unspecified+no_connect"))
    )
    (net (code "79") (name "unconnected-(U4-PC8-Pad39)") (class "Default")
      (node (ref "U4") (pin "39") (pinfunction "PC8_39") (pintype "unspecified+no_connect"))
    )
    (net (code "80") (name "unconnected-(U4-PC9-Pad40)") (class "Default")
      (node (ref "U4") (pin "40") (pinfunction "PC9_40") (pintype "unspecified+no_connect"))
    )
    (net (code "81") (name "unconnected-(U4-PC10-Pad51)") (class "Default")
      (node (ref "U4") (pin "51") (pinfunction "PC10_51") (pintype "unspecified+no_connect"))
    )
    (net (code "82") (name "unconnected-(U4-PC13-Pad2)") (class "Default")
      (node (ref "U4") (pin "2") (pinfunction "PC13_2") (pintype "unspecified+no_connect"))
    )
    (net (code "83") (name "unconnected-(U4-PC14-OSC32_IN-Pad3)") (class "Default")
      (node (ref "U4") (pin "3") (pinfunction "PC14-OSC32_IN_3") (pintype "unspecified+no_connect"))
    )
    (net (code "84") (name "unconnected-(U4-PC15-OSC32_OUT-Pad4)") (class "Default")
      (node (ref "U4") (pin "4") (pinfunction "PC15-OSC32_OUT_4") (pintype "unspecified+no_connect"))
    )
    (net (code "85") (name "unconnected-(U4-PD2-Pad54)") (class "Default")
      (node (ref "U4") (pin "54") (pinfunction "PD2_54") (pintype "unspecified+no_connect"))
    )
    (net (code "86") (name "unconnected-(U5-TAB-Pad4)") (class "Default")
      (node (ref "U5") (pin "4") (pinfunction "TAB_4") (pintype "unspecified+no_connect"))
    )
    (net (code "87") (name "unconnected-(USB1-ID-Pad4)") (class "Default")
      (node (ref "USB1") (pin "4") (pinfunction "ID_4") (pintype "input+no_connect"))
    )
  )
)
